# LEDs.net
KiCad netlist of a schematic drawn in Altium Designer
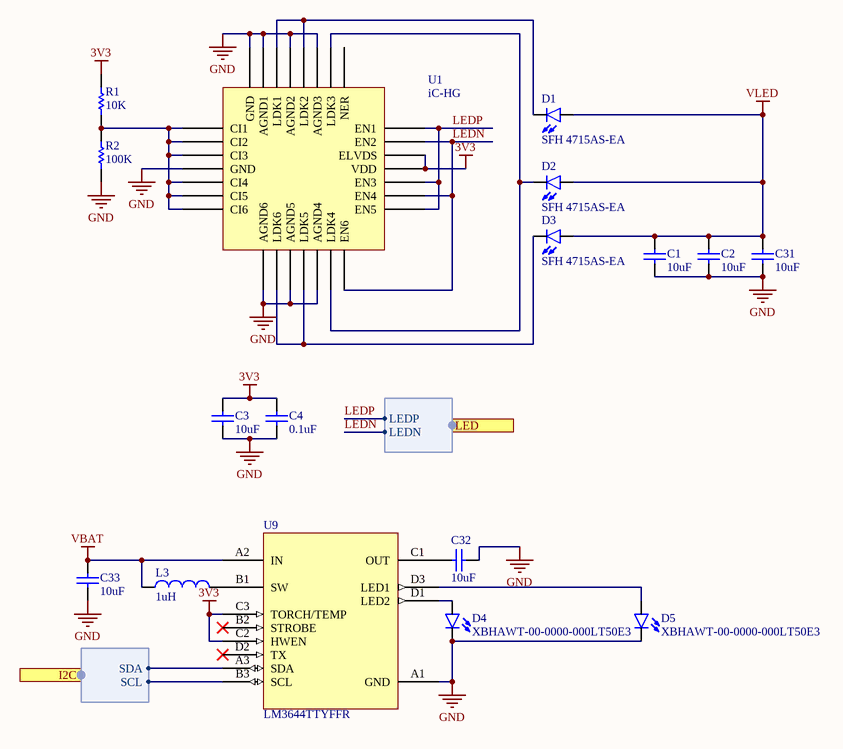
[diagram p0: LEDs.SchDoc]

(export (version "E")
  (design (tool "Eeschema 10.0.6"))
  (components
    (comp (ref "C1")
      (value "10uF")
      (footprint "C0402[1005X55]")
      (description "10uF 6.3V 20% 0402 (1005 Metric)")
      (fields (field (name "PARTNUMBER") "GRM155R60J106ME44D") (field (name "MANUFACTURER") "Murata"))
      (libsource (lib "Capacitors") (part "CAP_10uF_6.3V_0402_20%"))
    )
    (comp (ref "C2")
      (value "10uF")
      (footprint "C0402[1005X55]")
      (description "10uF 6.3V 20% 0402 (1005 Metric)")
      (fields (field (name "PARTNUMBER") "GRM155R60J106ME44D") (field (name "MANUFACTURER") "Murata"))
      (libsource (lib "Capacitors") (part "CAP_10uF_6.3V_0402_20%"))
    )
    (comp (ref "C3")
      (value "10uF")
      (footprint "C0402[1005X55]")
      (description "10uF 6.3V 20% 0402 (1005 Metric)")
      (fields (field (name "PARTNUMBER") "GRM155R60J106ME44D") (field (name "MANUFACTURER") "Murata"))
      (libsource (lib "Capacitors") (part "CAP_10uF_6.3V_0402_20%"))
    )
    (comp (ref "C4")
      (value "0.1uF")
      (footprint "C0201[0603X30]")
      (description "0.1uF 6.3V 10% 0201 (0603 Metric)")
      (fields (field (name "PARTNUMBER") "GRT033R60J104KE01D") (field (name "MANUFACTURER") "Murata"))
      (libsource (lib "Capacitors") (part "CAP_0.1uF_6.3V_0201_10%"))
    )
    (comp (ref "C31")
      (value "10uF")
      (footprint "C0402[1005X55]")
      (description "10uF 6.3V 20% 0402 (1005 Metric)")
      (fields (field (name "PARTNUMBER") "GRM155R60J106ME44D") (field (name "MANUFACTURER") "Murata"))
      (libsource (lib "Capacitors") (part "CAP_10uF_6.3V_0402_20%"))
    )
    (comp (ref "C32")
      (value "10uF")
      (footprint "C0402[1005X55]")
      (description "10uF 6.3V 20% 0402 (1005 Metric)")
      (fields (field (name "PARTNUMBER") "GRM155R60J106ME44D") (field (name "MANUFACTURER") "Murata"))
      (libsource (lib "Capacitors") (part "CAP_10uF_6.3V_0402_20%"))
    )
    (comp (ref "C33")
      (value "10uF")
      (footprint "C0402[1005X55]")
      (description "10uF 6.3V 20% 0402 (1005 Metric)")
      (fields (field (name "PARTNUMBER") "GRM155R60J106ME44D") (field (name "MANUFACTURER") "Murata"))
      (libsource (lib "Capacitors") (part "CAP_10uF_6.3V_0402_20%"))
    )
    (comp (ref "D1")
      (value "SFH 4715AS-EA")
      (footprint "SFH 4715AS")
      (fields (field (name "MANUFACTURER") "Osram"))
      (libsource (lib "LEDs") (part "SFH 4715AS-EA"))
    )
    (comp (ref "D2")
      (value "SFH 4715AS-EA")
      (footprint "SFH 4715AS")
      (fields (field (name "MANUFACTURER") "Osram"))
      (libsource (lib "LEDs") (part "SFH 4715AS-EA"))
    )
    (comp (ref "D3")
      (value "SFH 4715AS-EA")
      (footprint "SFH 4715AS")
      (fields (field (name "MANUFACTURER") "Osram"))
      (libsource (lib "LEDs") (part "SFH 4715AS-EA"))
    )
    (comp (ref "D4")
      (value "XBHAWT-00-0000-000LT50E3")
      (footprint "XBHAWT")
      (fields (field (name "MANUFACTURER") "Cree, Inc."))
      (libsource (lib "LEDs") (part "XBHAWT-00-0000-000LT50E3"))
    )
    (comp (ref "D5")
      (value "XBHAWT-00-0000-000LT50E3")
      (footprint "XBHAWT")
      (fields (field (name "MANUFACTURER") "Cree, Inc."))
      (libsource (lib "LEDs") (part "XBHAWT-00-0000-000LT50E3"))
    )
    (comp (ref "L3")
      (value "1uH")
      (footprint "IND0402")
      (description "1uH 20% 0.5A 0402")
      (fields (field (name "PARTNUMBER") "MLP1005M1R0DT0S1") (field (name "MANUFACTURER") "Murata"))
      (libsource (lib "Inductors") (part "IND_1uH_0.5A_0402_20%"))
    )
    (comp (ref "R1")
      (value "10K")
      (footprint "R0402[1005]")
      (description "10K 0.063W 1% 0402 (1005 Metric)")
      (fields (field (name "MANUFACTURER") "KOA Speer") (field (name "PARTNUMBER") "RK73H1ETTP1002F"))
      (libsource (lib "Resistors") (part "RES_10K_0402_1%"))
    )
    (comp (ref "R2")
      (value "100K")
      (footprint "R0402[1005]")
      (description "100K 0.063W 1% 0402 (1005 Metric)")
      (fields (field (name "MANUFACTURER") "KOA Speer") (field (name "PARTNUMBER") "RK73H1ETTP1003F"))
      (libsource (lib "Resistors") (part "RES_100K_0402_1%"))
    )
    (comp (ref "U1")
      (value "iC-HG")
      (footprint "QFN-28")
      (fields (field (name "PARTNUMBER") "iC-HG QFN28-5x5") (field (name "MANUFACTURER") "iC-Haus"))
      (libsource (lib "ICs") (part "iC-HG QFN28-5x5"))
    )
    (comp (ref "U9")
      (value "LM3644TTYFFR")
      (footprint "BGA-12")
      (description "LED Lighting Drivers 1.5 Amp LED driver")
      (fields (field (name "MANUFACTURER") "Texas Instruments"))
      (libsource (lib "ICs") (part "LM3644TTYFFR"))
    )
  )
  (nets
    (net (code "3") (name "/LEDN") (class "Default")
      (node (ref "U1") (pin "14") (pinfunction "EN6_14") (pintype "passive"))
      (node (ref "U1") (pin "16") (pinfunction "EN4_16") (pintype "passive"))
      (node (ref "U1") (pin "20") (pinfunction "EN2_20") (pintype "passive"))
    )
    (net (code "4") (name "/LEDP") (class "Default")
      (node (ref "U1") (pin "15") (pinfunction "EN5_15") (pintype "passive"))
      (node (ref "U1") (pin "17") (pinfunction "EN3_17") (pintype "passive"))
      (node (ref "U1") (pin "21") (pinfunction "EN1_21") (pintype "passive"))
    )
    (net (code "5") (name "/SCL") (class "Default")
      (node (ref "U9") (pin "B3") (pinfunction "SCL_B3") (pintype "bidirectional"))
    )
    (net (code "6") (name "/SDA") (class "Default")
      (node (ref "U9") (pin "A3") (pinfunction "SDA_A3") (pintype "bidirectional"))
    )
    (net (code "9") (name "3V3") (class "Default")
      (node (ref "C3") (pin "2") (pinfunction "2_2") (pintype "passive"))
      (node (ref "C4") (pin "2") (pinfunction "2_2") (pintype "passive"))
      (node (ref "R1") (pin "2") (pinfunction "2_2") (pintype "passive"))
      (node (ref "U1") (pin "18") (pinfunction "VDD_18") (pintype "passive"))
      (node (ref "U1") (pin "19") (pinfunction "ELVDS_19") (pintype "passive"))
      (node (ref "U9") (pin "C2") (pinfunction "HWEN_C2") (pintype "input"))
      (node (ref "U9") (pin "C3") (pinfunction "TORCH/TEMP_C3") (pintype "input"))
    )
    (net (code "10") (name "GND") (class "Default")
      (node (ref "C1") (pin "1") (pinfunction "1_1") (pintype "passive"))
      (node (ref "C2") (pin "1") (pinfunction "1_1") (pintype "passive"))
      (node (ref "C3") (pin "1") (pinfunction "1_1") (pintype "passive"))
      (node (ref "C31") (pin "1") (pinfunction "1_1") (pintype "passive"))
      (node (ref "C32") (pin "1") (pinfunction "1_1") (pintype "passive"))
      (node (ref "C33") (pin "1") (pinfunction "1_1") (pintype "passive"))
      (node (ref "C4") (pin "1") (pinfunction "1_1") (pintype "passive"))
      (node (ref "D4") (pin "C") (pinfunction "C_C") (pintype "passive"))
      (node (ref "D5") (pin "C") (pinfunction "C_C") (pintype "passive"))
      (node (ref "R2") (pin "1") (pinfunction "1_1") (pintype "passive"))
      (node (ref "U1") (pin "10") (pinfunction "AGND5_10") (pintype "passive"))
      (node (ref "U1") (pin "12") (pinfunction "AGND4_12") (pintype "passive"))
      (node (ref "U1") (pin "24") (pinfunction "AGND3_24") (pintype "passive"))
      (node (ref "U1") (pin "26") (pinfunction "AGND2_26") (pintype "passive"))
      (node (ref "U1") (pin "28") (pinfunction "AGND1_28") (pintype "passive"))
      (node (ref "U1") (pin "29") (pinfunction "GND_29") (pintype "passive"))
      (node (ref "U1") (pin "4") (pinfunction "GND_4") (pintype "passive"))
      (node (ref "U1") (pin "8") (pinfunction "AGND6_8") (pintype "passive"))
      (node (ref "U9") (pin "A1") (pinfunction "GND_A1") (pintype "power_in"))
    )
    (net (code "11") (name "Net-(U1-CI1)") (class "Default")
      (node (ref "R1") (pin "1") (pinfunction "1_1") (pintype "passive"))
      (node (ref "R2") (pin "2") (pinfunction "2_2") (pintype "passive"))
      (node (ref "U1") (pin "1") (pinfunction "CI1_1") (pintype "passive"))
      (node (ref "U1") (pin "2") (pinfunction "CI2_2") (pintype "passive"))
      (node (ref "U1") (pin "3") (pinfunction "CI3_3") (pintype "passive"))
      (node (ref "U1") (pin "5") (pinfunction "CI4_5") (pintype "passive"))
      (node (ref "U1") (pin "6") (pinfunction "CI5_6") (pintype "passive"))
      (node (ref "U1") (pin "7") (pinfunction "CI6_7") (pintype "passive"))
    )
    (net (code "12") (name "Net-(U1-LDK1)") (class "Default")
      (node (ref "D1") (pin "C") (pinfunction "C_C") (pintype "passive"))
      (node (ref "U1") (pin "25") (pinfunction "LDK2_25") (pintype "passive"))
      (node (ref "U1") (pin "27") (pinfunction "LDK1_27") (pintype "passive"))
    )
    (net (code "13") (name "Net-(U1-LDK3)") (class "Default")
      (node (ref "D2") (pin "C") (pinfunction "C_C") (pintype "passive"))
      (node (ref "U1") (pin "13") (pinfunction "LDK4_13") (pintype "passive"))
      (node (ref "U1") (pin "23") (pinfunction "LDK3_23") (pintype "passive"))
    )
    (net (code "14") (name "Net-(U1-LDK5)") (class "Default")
      (node (ref "D3") (pin "C") (pinfunction "C_C") (pintype "passive"))
      (node (ref "U1") (pin "11") (pinfunction "LDK5_11") (pintype "passive"))
      (node (ref "U1") (pin "9") (pinfunction "LDK6_9") (pintype "passive"))
    )
    (net (code "15") (name "Net-(U9-LED1)") (class "Default")
      (node (ref "D5") (pin "A") (pinfunction "A_A") (pintype "passive"))
      (node (ref "U9") (pin "D3") (pinfunction "LED1_D3") (pintype "output"))
    )
    (net (code "16") (name "Net-(U9-LED2)") (class "Default")
      (node (ref "D4") (pin "A") (pinfunction "A_A") (pintype "passive"))
      (node (ref "U9") (pin "D1") (pinfunction "LED2_D1") (pintype "output"))
    )
    (net (code "17") (name "Net-(U9-OUT)") (class "Default")
      (node (ref "C32") (pin "2") (pinfunction "2_2") (pintype "passive"))
      (node (ref "U9") (pin "C1") (pinfunction "OUT_C1") (pintype "power_in"))
    )
    (net (code "18") (name "Net-(U9-SW)") (class "Default")
      (node (ref "L3") (pin "2") (pinfunction "2_2") (pintype "passive"))
      (node (ref "U9") (pin "B1") (pinfunction "SW_B1") (pintype "power_in"))
    )
    (net (code "19") (name "VBAT") (class "Default")
      (node (ref "C33") (pin "2") (pinfunction "2_2") (pintype "passive"))
      (node (ref "L3") (pin "1") (pinfunction "1_1") (pintype "passive"))
      (node (ref "U9") (pin "A2") (pinfunction "IN_A2") (pintype "power_in"))
    )
    (net (code "20") (name "VLED") (class "Default")
      (node (ref "C1") (pin "2") (pinfunction "2_2") (pintype "passive"))
      (node (ref "C2") (pin "2") (pinfunction "2_2") (pintype "passive"))
      (node (ref "C31") (pin "2") (pinfunction "2_2") (pintype "passive"))
      (node (ref "D1") (pin "A") (pinfunction "A_A") (pintype "passive"))
      (node (ref "D2") (pin "A") (pinfunction "A_A") (pintype "passive"))
      (node (ref "D3") (pin "A") (pinfunction "A_A") (pintype "passive"))
    )
    (net (code "21") (name "unconnected-(U1-NER-Pad22)") (class "Default")
      (node (ref "U1") (pin "22") (pinfunction "NER_22") (pintype "passive"))
    )
    (net (code "22") (name "unconnected-(U9-STROBE-PadB2)") (class "Default")
      (node (ref "U9") (pin "B2") (pinfunction "STROBE_B2") (pintype "input+no_connect"))
    )
    (net (code "23") (name "unconnected-(U9-TX-PadD2)") (class "Default")
      (node (ref "U9") (pin "D2") (pinfunction "TX_D2") (pintype "input+no_connect"))
    )
  )
)
